# Bf706_DSP.net
KiCad netlist of a schematic drawn in Altium Designer
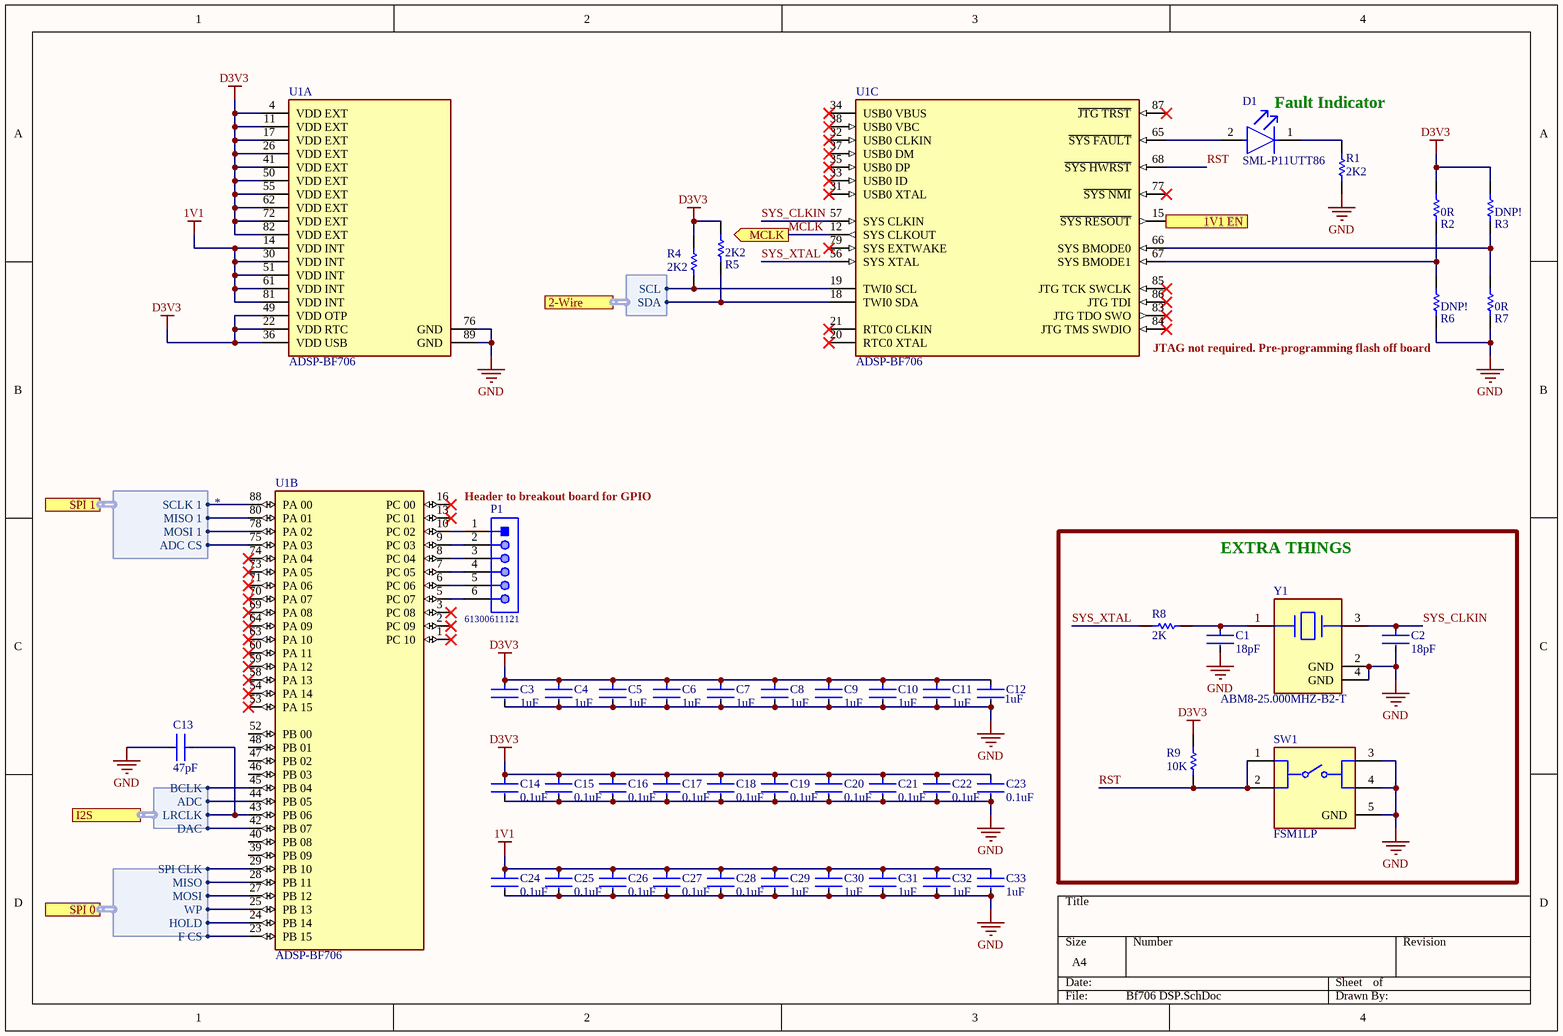
[diagram p0: Bf706 DSP.SchDoc]

(export (version "E")
  (design (tool "Eeschema 10.0.6"))
  (components
    (comp (ref "C1")
      (value "18pF")
      (footprint "FP-GRM15-MFG")
      (description "CAP CER 0.1UF 16V X7R 0402")
      (fields (field (name "MANUFACTURER PART NUMBER") "GRM155R71C104KA88D") (field (name "TOLERANCE") "10%"))
      (libsource (lib "Altium Content Vault") (part "236180d848d6139a670b325ea6854c9"))
    )
    (comp (ref "C2")
      (value "18pF")
      (footprint "FP-GRM15-MFG")
      (description "CAP CER 0.1UF 16V X7R 0402")
      (fields (field (name "MANUFACTURER PART NUMBER") "GRM155R71C104KA88D") (field (name "TOLERANCE") "10%"))
      (libsource (lib "Altium Content Vault") (part "236180d848d6139a670b325ea6854c9"))
    )
    (comp (ref "C3")
      (value "1uF")
      (footprint "FP-GRM15-MFG")
      (description "CAP CER 0.1UF 16V X7R 0402")
      (fields (field (name "MANUFACTURER PART NUMBER") "GRM155R71C104KA88D") (field (name "TOLERANCE") "10%"))
      (libsource (lib "Altium Content Vault") (part "236180d848d6139a670b325ea6854c9"))
    )
    (comp (ref "C4")
      (value "1uF")
      (footprint "FP-GRM15-MFG")
      (description "CAP CER 0.1UF 16V X7R 0402")
      (fields (field (name "MANUFACTURER PART NUMBER") "GRM155R71C104KA88D") (field (name "TOLERANCE") "10%"))
      (libsource (lib "Altium Content Vault") (part "236180d848d6139a670b325ea6854c9"))
    )
    (comp (ref "C5")
      (value "1uF")
      (footprint "FP-GRM15-MFG")
      (description "CAP CER 0.1UF 16V X7R 0402")
      (fields (field (name "MANUFACTURER PART NUMBER") "GRM155R71C104KA88D") (field (name "TOLERANCE") "10%"))
      (libsource (lib "Altium Content Vault") (part "236180d848d6139a670b325ea6854c9"))
    )
    (comp (ref "C6")
      (value "1uF")
      (footprint "FP-GRM15-MFG")
      (description "CAP CER 0.1UF 16V X7R 0402")
      (fields (field (name "MANUFACTURER PART NUMBER") "GRM155R71C104KA88D") (field (name "TOLERANCE") "10%"))
      (libsource (lib "Altium Content Vault") (part "236180d848d6139a670b325ea6854c9"))
    )
    (comp (ref "C7")
      (value "1uF")
      (footprint "FP-GRM15-MFG")
      (description "CAP CER 0.1UF 16V X7R 0402")
      (fields (field (name "MANUFACTURER PART NUMBER") "GRM155R71C104KA88D") (field (name "TOLERANCE") "10%"))
      (libsource (lib "Altium Content Vault") (part "236180d848d6139a670b325ea6854c9"))
    )
    (comp (ref "C8")
      (value "1uF")
      (footprint "FP-GRM15-MFG")
      (description "CAP CER 0.1UF 16V X7R 0402")
      (fields (field (name "MANUFACTURER PART NUMBER") "GRM155R71C104KA88D") (field (name "TOLERANCE") "10%"))
      (libsource (lib "Altium Content Vault") (part "236180d848d6139a670b325ea6854c9"))
    )
    (comp (ref "C9")
      (value "1uF")
      (footprint "FP-GRM15-MFG")
      (description "CAP CER 0.1UF 16V X7R 0402")
      (fields (field (name "MANUFACTURER PART NUMBER") "GRM155R71C104KA88D") (field (name "TOLERANCE") "10%"))
      (libsource (lib "Altium Content Vault") (part "236180d848d6139a670b325ea6854c9"))
    )
    (comp (ref "C10")
      (value "1uF")
      (footprint "FP-GRM15-MFG")
      (description "CAP CER 0.1UF 16V X7R 0402")
      (fields (field (name "MANUFACTURER PART NUMBER") "GRM155R71C104KA88D") (field (name "TOLERANCE") "10%"))
      (libsource (lib "Altium Content Vault") (part "236180d848d6139a670b325ea6854c9"))
    )
    (comp (ref "C11")
      (value "1uF")
      (footprint "FP-GRM15-MFG")
      (description "CAP CER 0.1UF 16V X7R 0402")
      (fields (field (name "MANUFACTURER PART NUMBER") "GRM155R71C104KA88D") (field (name "TOLERANCE") "10%"))
      (libsource (lib "Altium Content Vault") (part "236180d848d6139a670b325ea6854c9"))
    )
    (comp (ref "C12")
      (value "1uF")
      (footprint "FP-GRM15-MFG")
      (description "CAP CER 0.1UF 16V X7R 0402")
      (fields (field (name "MANUFACTURER PART NUMBER") "GRM155R71C104KA88D") (field (name "TOLERANCE") "10%"))
      (libsource (lib "Altium Content Vault") (part "236180d848d6139a670b325ea6854c9"))
    )
    (comp (ref "C13")
      (value "47pF")
      (footprint "FP-GRM15-MFG")
      (description "CAP CER 0.1UF 16V X7R 0402")
      (fields (field (name "MANUFACTURER PART NUMBER") "GRM155R71C104KA88D") (field (name "TOLERANCE") "10%"))
      (libsource (lib "Altium Content Vault") (part "236180d848d6139a670b325ea6854c9"))
    )
    (comp (ref "C14")
      (value "0.1uF")
      (footprint "FP-GRM15-MFG")
      (description "CAP CER 0.1UF 16V X7R 0402")
      (fields (field (name "MANUFACTURER PART NUMBER") "GRM155R71C104KA88D") (field (name "TOLERANCE") "10%"))
      (libsource (lib "Altium Content Vault") (part "236180d848d6139a670b325ea6854c9"))
    )
    (comp (ref "C15")
      (value "0.1uF")
      (footprint "FP-GRM15-MFG")
      (description "CAP CER 0.1UF 16V X7R 0402")
      (fields (field (name "MANUFACTURER PART NUMBER") "GRM155R71C104KA88D") (field (name "TOLERANCE") "10%"))
      (libsource (lib "Altium Content Vault") (part "236180d848d6139a670b325ea6854c9"))
    )
    (comp (ref "C16")
      (value "0.1uF")
      (footprint "FP-GRM15-MFG")
      (description "CAP CER 0.1UF 16V X7R 0402")
      (fields (field (name "MANUFACTURER PART NUMBER") "GRM155R71C104KA88D") (field (name "TOLERANCE") "10%"))
      (libsource (lib "Altium Content Vault") (part "236180d848d6139a670b325ea6854c9"))
    )
    (comp (ref "C17")
      (value "0.1uF")
      (footprint "FP-GRM15-MFG")
      (description "CAP CER 0.1UF 16V X7R 0402")
      (fields (field (name "MANUFACTURER PART NUMBER") "GRM155R71C104KA88D") (field (name "TOLERANCE") "10%"))
      (libsource (lib "Altium Content Vault") (part "236180d848d6139a670b325ea6854c9"))
    )
    (comp (ref "C18")
      (value "0.1uF")
      (footprint "FP-GRM15-MFG")
      (description "CAP CER 0.1UF 16V X7R 0402")
      (fields (field (name "MANUFACTURER PART NUMBER") "GRM155R71C104KA88D") (field (name "TOLERANCE") "10%"))
      (libsource (lib "Altium Content Vault") (part "236180d848d6139a670b325ea6854c9"))
    )
    (comp (ref "C19")
      (value "0.1uF")
      (footprint "FP-GRM15-MFG")
      (description "CAP CER 0.1UF 16V X7R 0402")
      (fields (field (name "MANUFACTURER PART NUMBER") "GRM155R71C104KA88D") (field (name "TOLERANCE") "10%"))
      (libsource (lib "Altium Content Vault") (part "236180d848d6139a670b325ea6854c9"))
    )
    (comp (ref "C20")
      (value "0.1uF")
      (footprint "FP-GRM15-MFG")
      (description "CAP CER 0.1UF 16V X7R 0402")
      (fields (field (name "MANUFACTURER PART NUMBER") "GRM155R71C104KA88D") (field (name "TOLERANCE") "10%"))
      (libsource (lib "Altium Content Vault") (part "236180d848d6139a670b325ea6854c9"))
    )
    (comp (ref "C21")
      (value "0.1uF")
      (footprint "FP-GRM15-MFG")
      (description "CAP CER 0.1UF 16V X7R 0402")
      (fields (field (name "MANUFACTURER PART NUMBER") "GRM155R71C104KA88D") (field (name "TOLERANCE") "10%"))
      (libsource (lib "Altium Content Vault") (part "236180d848d6139a670b325ea6854c9"))
    )
    (comp (ref "C22")
      (value "0.1uF")
      (footprint "FP-GRM15-MFG")
      (description "CAP CER 0.1UF 16V X7R 0402")
      (fields (field (name "MANUFACTURER PART NUMBER") "GRM155R71C104KA88D") (field (name "TOLERANCE") "10%"))
      (libsource (lib "Altium Content Vault") (part "236180d848d6139a670b325ea6854c9"))
    )
    (comp (ref "C23")
      (value "0.1uF")
      (footprint "FP-GRM15-MFG")
      (description "CAP CER 0.1UF 16V X7R 0402")
      (fields (field (name "MANUFACTURER PART NUMBER") "GRM155R71C104KA88D") (field (name "TOLERANCE") "10%"))
      (libsource (lib "Altium Content Vault") (part "236180d848d6139a670b325ea6854c9"))
    )
    (comp (ref "C24")
      (value "0.1uF")
      (footprint "FP-GRM15-MFG")
      (description "CAP CER 0.1UF 16V X7R 0402")
      (fields (field (name "MANUFACTURER PART NUMBER") "GRM155R71C104KA88D") (field (name "TOLERANCE") "10%"))
      (libsource (lib "Altium Content Vault") (part "236180d848d6139a670b325ea6854c9"))
    )
    (comp (ref "C25")
      (value "0.1uF")
      (footprint "FP-GRM15-MFG")
      (description "CAP CER 0.1UF 16V X7R 0402")
      (fields (field (name "MANUFACTURER PART NUMBER") "GRM155R71C104KA88D") (field (name "TOLERANCE") "10%"))
      (libsource (lib "Altium Content Vault") (part "236180d848d6139a670b325ea6854c9"))
    )
    (comp (ref "C26")
      (value "0.1uF")
      (footprint "FP-GRM15-MFG")
      (description "CAP CER 0.1UF 16V X7R 0402")
      (fields (field (name "MANUFACTURER PART NUMBER") "GRM155R71C104KA88D") (field (name "TOLERANCE") "10%"))
      (libsource (lib "Altium Content Vault") (part "236180d848d6139a670b325ea6854c9"))
    )
    (comp (ref "C27")
      (value "0.1uF")
      (footprint "FP-GRM15-MFG")
      (description "CAP CER 0.1UF 16V X7R 0402")
      (fields (field (name "MANUFACTURER PART NUMBER") "GRM155R71C104KA88D") (field (name "TOLERANCE") "10%"))
      (libsource (lib "Altium Content Vault") (part "236180d848d6139a670b325ea6854c9"))
    )
    (comp (ref "C28")
      (value "0.1uF")
      (footprint "FP-GRM15-MFG")
      (description "CAP CER 0.1UF 16V X7R 0402")
      (fields (field (name "MANUFACTURER PART NUMBER") "GRM155R71C104KA88D") (field (name "TOLERANCE") "10%"))
      (libsource (lib "Altium Content Vault") (part "236180d848d6139a670b325ea6854c9"))
    )
    (comp (ref "C29")
      (value "1uF")
      (footprint "FP-GRM15-MFG")
      (description "CAP CER 0.1UF 16V X7R 0402")
      (fields (field (name "MANUFACTURER PART NUMBER") "GRM155R71C104KA88D") (field (name "TOLERANCE") "10%"))
      (libsource (lib "Altium Content Vault") (part "236180d848d6139a670b325ea6854c9"))
    )
    (comp (ref "C30")
      (value "1uF")
      (footprint "FP-GRM15-MFG")
      (description "CAP CER 0.1UF 16V X7R 0402")
      (fields (field (name "MANUFACTURER PART NUMBER") "GRM155R71C104KA88D") (field (name "TOLERANCE") "10%"))
      (libsource (lib "Altium Content Vault") (part "236180d848d6139a670b325ea6854c9"))
    )
    (comp (ref "C31")
      (value "1uF")
      (footprint "FP-GRM15-MFG")
      (description "CAP CER 0.1UF 16V X7R 0402")
      (fields (field (name "MANUFACTURER PART NUMBER") "GRM155R71C104KA88D") (field (name "TOLERANCE") "10%"))
      (libsource (lib "Altium Content Vault") (part "236180d848d6139a670b325ea6854c9"))
    )
    (comp (ref "C32")
      (value "1uF")
      (footprint "FP-GRM15-MFG")
      (description "CAP CER 0.1UF 16V X7R 0402")
      (fields (field (name "MANUFACTURER PART NUMBER") "GRM155R71C104KA88D") (field (name "TOLERANCE") "10%"))
      (libsource (lib "Altium Content Vault") (part "236180d848d6139a670b325ea6854c9"))
    )
    (comp (ref "C33")
      (value "1uF")
      (footprint "FP-GRM15-MFG")
      (description "CAP CER 0.1UF 16V X7R 0402")
      (fields (field (name "MANUFACTURER PART NUMBER") "GRM155R71C104KA88D") (field (name "TOLERANCE") "10%"))
      (libsource (lib "Altium Content Vault") (part "236180d848d6139a670b325ea6854c9"))
    )
    (comp (ref "D1")
      (value "SML-P11UTT86")
      (footprint "FP-SML-P11UTT86-MFG")
      (description "LED RED CLEAR 1006 SMD")
      (libsource (lib "Altium Content Vault") (part "8706943c75ba83719d021d2fdc84c58"))
    )
    (comp (ref "P1")
      (value "61300611121")
      (footprint "61300611121")
      (description "THT Vertical Pin Header WR-PHD, Pitch 2.54 mm, Single Row, 6 pins")
      (fields (field (name "MANUFACTURER") "Wurth Elektronik") (field (name "PUBLISHER") "WurthElektronik"))
      (libsource (lib "Altium Content Vault") (part "WE-CN-1P-M-R6"))
    )
    (comp (ref "R1")
      (value "2K2")
      (footprint "RESC1005X40X25LL05T05")
      (description "Chip Resistor, 0 Ohm, 0.1 W, -55 to 155 degC, 0402 (1005 Metric), RoHS, Tape and Reel")
      (fields (field (name "MANUFACTURER") "Panasonic") (field (name "TOLERANCE") "5%"))
      (libsource (lib "Altium Content Vault") (part "RES-2"))
    )
    (comp (ref "R2")
      (value "0R")
      (footprint "RESC1005X40X25LL05T05")
      (description "Chip Resistor, 0 Ohm, 0.1 W, -55 to 155 degC, 0402 (1005 Metric), RoHS, Tape and Reel")
      (fields (field (name "MANUFACTURER") "Panasonic") (field (name "TOLERANCE") "5%"))
      (libsource (lib "Altium Content Vault") (part "RES-2"))
    )
    (comp (ref "R3")
      (value "DNP!")
      (footprint "RESC1005X40X25LL05T05")
      (description "Chip Resistor, 0 Ohm, 0.1 W, -55 to 155 degC, 0402 (1005 Metric), RoHS, Tape and Reel")
      (fields (field (name "MANUFACTURER") "Panasonic") (field (name "TOLERANCE") "5%"))
      (libsource (lib "Altium Content Vault") (part "RES-2"))
    )
    (comp (ref "R4")
      (value "2K2")
      (footprint "RESC1005X40X25LL05T05")
      (description "Chip Resistor, 0 Ohm, 0.1 W, -55 to 155 degC, 0402 (1005 Metric), RoHS, Tape and Reel")
      (fields (field (name "MANUFACTURER") "Panasonic") (field (name "TOLERANCE") "5%"))
      (libsource (lib "Altium Content Vault") (part "RES-2"))
    )
    (comp (ref "R5")
      (value "2K2")
      (footprint "RESC1005X40X25LL05T05")
      (description "Chip Resistor, 0 Ohm, 0.1 W, -55 to 155 degC, 0402 (1005 Metric), RoHS, Tape and Reel")
      (fields (field (name "MANUFACTURER") "Panasonic") (field (name "TOLERANCE") "5%"))
      (libsource (lib "Altium Content Vault") (part "RES-2"))
    )
    (comp (ref "R6")
      (value "DNP!")
      (footprint "RESC1005X40X25LL05T05")
      (description "Chip Resistor, 0 Ohm, 0.1 W, -55 to 155 degC, 0402 (1005 Metric), RoHS, Tape and Reel")
      (fields (field (name "MANUFACTURER") "Panasonic") (field (name "TOLERANCE") "5%"))
      (libsource (lib "Altium Content Vault") (part "RES-2"))
    )
    (comp (ref "R7")
      (value "0R")
      (footprint "RESC1005X40X25LL05T05")
      (description "Chip Resistor, 0 Ohm, 0.1 W, -55 to 155 degC, 0402 (1005 Metric), RoHS, Tape and Reel")
      (fields (field (name "MANUFACTURER") "Panasonic") (field (name "TOLERANCE") "5%"))
      (libsource (lib "Altium Content Vault") (part "RES-2"))
    )
    (comp (ref "R8")
      (value "2K")
      (footprint "RESC1005X40X25LL05T05")
      (description "Chip Resistor, 0 Ohm, 0.1 W, -55 to 155 degC, 0402 (1005 Metric), RoHS, Tape and Reel")
      (fields (field (name "MANUFACTURER") "Panasonic") (field (name "TOLERANCE") "5%"))
      (libsource (lib "Altium Content Vault") (part "RES-2"))
    )
    (comp (ref "R9")
      (value "10K")
      (footprint "RESC1005X40X25LL05T05")
      (description "Chip Resistor, 0 Ohm, 0.1 W, -55 to 155 degC, 0402 (1005 Metric), RoHS, Tape and Reel")
      (fields (field (name "MANUFACTURER") "Panasonic") (field (name "TOLERANCE") "5%"))
      (libsource (lib "Altium Content Vault") (part "RES-2"))
    )
    (comp (ref "SW1")
      (value "FSM1LP")
      (footprint "FP-FSM1LP-MFG")
      (description "SWITCH TACTILE SPST-NO 0.05A 24V")
      (libsource (lib "Altium Content Vault") (part "3a9e64be5c1b186b34f28721102267a"))
    )
    (comp (ref "U1")
      (value "ADSP-BF706")
      (footprint "FP-CP-88-8-IPC_C")
      (description "IC DSP LP 128KB L2SR 88LFCSP")
      (libsource (lib "Altium Content Vault") (part "f148b48c6e4e4aed1bc29808ef88166"))
    )
    (comp (ref "Y1")
      (value "ABM8-25.000MHZ-B2-T")
      (footprint "FP-ABM8-MFG")
      (description "Crystal 25MHz ±20ppm 18pF SMD-4 3.2mm x 2.5mm")
      (fields (field (name "TOLERANCE") "20ppm"))
      (libsource (lib "Altium Content Vault") (part "dfdb7f9a12507849fb681da9a70121c"))
    )
  )
  (nets
    (net (code "6") (name "/1V1 EN") (class "Default")
      (node (ref "U1") (pin "15") (pinfunction "~{SYS_RESOUT}_15") (pintype "output"))
    )
    (net (code "7") (name "/ADC") (class "Default")
      (node (ref "U1") (pin "44") (pinfunction "PB_05_44") (pintype "bidirectional"))
    )
    (net (code "8") (name "/ADC CS") (class "Default")
      (node (ref "U1") (pin "75") (pinfunction "PA_03_75") (pintype "bidirectional"))
    )
    (net (code "9") (name "/BCLK") (class "Default")
      (node (ref "U1") (pin "45") (pinfunction "PB_04_45") (pintype "bidirectional"))
    )
    (net (code "10") (name "/DAC") (class "Default")
      (node (ref "U1") (pin "42") (pinfunction "PB_07_42") (pintype "bidirectional"))
    )
    (net (code "11") (name "/F CS") (class "Default")
      (node (ref "U1") (pin "23") (pinfunction "PB_15_23") (pintype "bidirectional"))
    )
    (net (code "12") (name "/HOLD") (class "Default")
      (node (ref "U1") (pin "24") (pinfunction "PB_14_24") (pintype "bidirectional"))
    )
    (net (code "13") (name "/LRCLK") (class "Default")
      (node (ref "C13") (pin "2") (pinfunction "2_2") (pintype "passive"))
      (node (ref "U1") (pin "43") (pinfunction "PB_06_43") (pintype "bidirectional"))
    )
    (net (code "14") (name "/MCLK") (class "Default")
      (node (ref "U1") (pin "12") (pinfunction "SYS_CLKOUT_12") (pintype "output"))
    )
    (net (code "15") (name "/MISO") (class "Default")
      (node (ref "U1") (pin "28") (pinfunction "PB_11_28") (pintype "bidirectional"))
    )
    (net (code "16") (name "/MISO 1") (class "Default")
      (node (ref "U1") (pin "80") (pinfunction "PA_01_80") (pintype "bidirectional"))
    )
    (net (code "17") (name "/MOSI") (class "Default")
      (node (ref "U1") (pin "27") (pinfunction "PB_12_27") (pintype "bidirectional"))
    )
    (net (code "18") (name "/MOSI 1") (class "Default")
      (node (ref "U1") (pin "78") (pinfunction "PA_02_78") (pintype "bidirectional"))
    )
    (net (code "19") (name "/RST") (class "Default")
      (node (ref "R9") (pin "1") (pinfunction "1_1") (pintype "passive"))
      (node (ref "SW1") (pin "1") (pinfunction "1_1") (pintype "passive"))
      (node (ref "SW1") (pin "2") (pinfunction "2_2") (pintype "passive"))
      (node (ref "U1") (pin "68") (pinfunction "~{SYS_HWRST}_68") (pintype "input"))
    )
    (net (code "20") (name "/SCL") (class "Default")
      (node (ref "R4") (pin "1") (pinfunction "1_1") (pintype "passive"))
      (node (ref "U1") (pin "19") (pinfunction "TWI0_SCL_19") (pintype "passive"))
    )
    (net (code "21") (name "/SCLK 1") (class "Default")
      (node (ref "U1") (pin "88") (pinfunction "PA_00_88") (pintype "bidirectional"))
    )
    (net (code "22") (name "/SDA") (class "Default")
      (node (ref "R5") (pin "1") (pinfunction "1_1") (pintype "passive"))
      (node (ref "U1") (pin "18") (pinfunction "TWI0_SDA_18") (pintype "passive"))
    )
    (net (code "23") (name "/SPI CLK") (class "Default")
      (node (ref "U1") (pin "29") (pinfunction "PB_10_29") (pintype "bidirectional"))
    )
    (net (code "24") (name "/SYS_CLKIN") (class "Default")
      (node (ref "C2") (pin "2") (pinfunction "2_2") (pintype "passive"))
      (node (ref "U1") (pin "57") (pinfunction "SYS_CLKIN_57") (pintype "input"))
      (node (ref "Y1") (pin "3") (pinfunction "3_3") (pintype "passive"))
    )
    (net (code "25") (name "/SYS_XTAL") (class "Default")
      (node (ref "R8") (pin "2") (pinfunction "2_2") (pintype "passive"))
      (node (ref "U1") (pin "56") (pinfunction "SYS_XTAL_56") (pintype "input"))
    )
    (net (code "26") (name "/WP") (class "Default")
      (node (ref "U1") (pin "25") (pinfunction "PB_13_25") (pintype "bidirectional"))
    )
    (net (code "31") (name "1V1") (class "Default")
      (node (ref "C24") (pin "2") (pinfunction "2_2") (pintype "passive"))
      (node (ref "C25") (pin "2") (pinfunction "2_2") (pintype "passive"))
      (node (ref "C26") (pin "2") (pinfunction "2_2") (pintype "passive"))
      (node (ref "C27") (pin "2") (pinfunction "2_2") (pintype "passive"))
      (node (ref "C28") (pin "2") (pinfunction "2_2") (pintype "passive"))
      (node (ref "C29") (pin "2") (pinfunction "2_2") (pintype "passive"))
      (node (ref "C30") (pin "2") (pinfunction "2_2") (pintype "passive"))
      (node (ref "C31") (pin "2") (pinfunction "2_2") (pintype "passive"))
      (node (ref "C32") (pin "2") (pinfunction "2_2") (pintype "passive"))
      (node (ref "C33") (pin "2") (pinfunction "2_2") (pintype "passive"))
      (node (ref "U1") (pin "14") (pinfunction "VDD_INT_14") (pintype "power_in"))
      (node (ref "U1") (pin "30") (pinfunction "VDD_INT_30") (pintype "power_in"))
      (node (ref "U1") (pin "51") (pinfunction "VDD_INT_51") (pintype "power_in"))
      (node (ref "U1") (pin "61") (pinfunction "VDD_INT_61") (pintype "power_in"))
      (node (ref "U1") (pin "81") (pinfunction "VDD_INT_81") (pintype "power_in"))
    )
    (net (code "32") (name "D3V3") (class "Default")
      (node (ref "C10") (pin "2") (pinfunction "2_2") (pintype "passive"))
      (node (ref "C11") (pin "2") (pinfunction "2_2") (pintype "passive"))
      (node (ref "C12") (pin "2") (pinfunction "2_2") (pintype "passive"))
      (node (ref "C14") (pin "2") (pinfunction "2_2") (pintype "passive"))
      (node (ref "C15") (pin "2") (pinfunction "2_2") (pintype "passive"))
      (node (ref "C16") (pin "2") (pinfunction "2_2") (pintype "passive"))
      (node (ref "C17") (pin "2") (pinfunction "2_2") (pintype "passive"))
      (node (ref "C18") (pin "2") (pinfunction "2_2") (pintype "passive"))
      (node (ref "C19") (pin "2") (pinfunction "2_2") (pintype "passive"))
      (node (ref "C20") (pin "2") (pinfunction "2_2") (pintype "passive"))
      (node (ref "C21") (pin "2") (pinfunction "2_2") (pintype "passive"))
      (node (ref "C22") (pin "2") (pinfunction "2_2") (pintype "passive"))
      (node (ref "C23") (pin "2") (pinfunction "2_2") (pintype "passive"))
      (node (ref "C3") (pin "2") (pinfunction "2_2") (pintype "passive"))
      (node (ref "C4") (pin "2") (pinfunction "2_2") (pintype "passive"))
      (node (ref "C5") (pin "2") (pinfunction "2_2") (pintype "passive"))
      (node (ref "C6") (pin "2") (pinfunction "2_2") (pintype "passive"))
      (node (ref "C7") (pin "2") (pinfunction "2_2") (pintype "passive"))
      (node (ref "C8") (pin "2") (pinfunction "2_2") (pintype "passive"))
      (node (ref "C9") (pin "2") (pinfunction "2_2") (pintype "passive"))
      (node (ref "R2") (pin "2") (pinfunction "2_2") (pintype "passive"))
      (node (ref "R3") (pin "2") (pinfunction "2_2") (pintype "passive"))
      (node (ref "R4") (pin "2") (pinfunction "2_2") (pintype "passive"))
      (node (ref "R5") (pin "2") (pinfunction "2_2") (pintype "passive"))
      (node (ref "R9") (pin "2") (pinfunction "2_2") (pintype "passive"))
      (node (ref "U1") (pin "11") (pinfunction "VDD_EXT_11") (pintype "power_in"))
      (node (ref "U1") (pin "17") (pinfunction "VDD_EXT_17") (pintype "power_in"))
      (node (ref "U1") (pin "22") (pinfunction "VDD_RTC_22") (pintype "power_in"))
      (node (ref "U1") (pin "26") (pinfunction "VDD_EXT_26") (pintype "power_in"))
      (node (ref "U1") (pin "36") (pinfunction "VDD_USB_36") (pintype "power_in"))
      (node (ref "U1") (pin "4") (pinfunction "VDD_EXT_4") (pintype "power_in"))
      (node (ref "U1") (pin "41") (pinfunction "VDD_EXT_41") (pintype "power_in"))
      (node (ref "U1") (pin "49") (pinfunction "VDD_OTP_49") (pintype "power_in"))
      (node (ref "U1") (pin "50") (pinfunction "VDD_EXT_50") (pintype "power_in"))
      (node (ref "U1") (pin "55") (pinfunction "VDD_EXT_55") (pintype "power_in"))
      (node (ref "U1") (pin "62") (pinfunction "VDD_EXT_62") (pintype "power_in"))
      (node (ref "U1") (pin "72") (pinfunction "VDD_EXT_72") (pintype "power_in"))
      (node (ref "U1") (pin "82") (pinfunction "VDD_EXT_82") (pintype "power_in"))
    )
    (net (code "33") (name "GND") (class "Default")
      (node (ref "C1") (pin "1") (pinfunction "1_1") (pintype "passive"))
      (node (ref "C10") (pin "1") (pinfunction "1_1") (pintype "passive"))
      (node (ref "C11") (pin "1") (pinfunction "1_1") (pintype "passive"))
      (node (ref "C12") (pin "1") (pinfunction "1_1") (pintype "passive"))
      (node (ref "C13") (pin "1") (pinfunction "1_1") (pintype "passive"))
      (node (ref "C14") (pin "1") (pinfunction "1_1") (pintype "passive"))
      (node (ref "C15") (pin "1") (pinfunction "1_1") (pintype "passive"))
      (node (ref "C16") (pin "1") (pinfunction "1_1") (pintype "passive"))
      (node (ref "C17") (pin "1") (pinfunction "1_1") (pintype "passive"))
      (node (ref "C18") (pin "1") (pinfunction "1_1") (pintype "passive"))
      (node (ref "C19") (pin "1") (pinfunction "1_1") (pintype "passive"))
      (node (ref "C2") (pin "1") (pinfunction "1_1") (pintype "passive"))
      (node (ref "C20") (pin "1") (pinfunction "1_1") (pintype "passive"))
      (node (ref "C21") (pin "1") (pinfunction "1_1") (pintype "passive"))
      (node (ref "C22") (pin "1") (pinfunction "1_1") (pintype "passive"))
      (node (ref "C23") (pin "1") (pinfunction "1_1") (pintype "passive"))
      (node (ref "C24") (pin "1") (pinfunction "1_1") (pintype "passive"))
      (node (ref "C25") (pin "1") (pinfunction "1_1") (pintype "passive"))
      (node (ref "C26") (pin "1") (pinfunction "1_1") (pintype "passive"))
      (node (ref "C27") (pin "1") (pinfunction "1_1") (pintype "passive"))
      (node (ref "C28") (pin "1") (pinfunction "1_1") (pintype "passive"))
      (node (ref "C29") (pin "1") (pinfunction "1_1") (pintype "passive"))
      (node (ref "C3") (pin "1") (pinfunction "1_1") (pintype "passive"))
      (node (ref "C30") (pin "1") (pinfunction "1_1") (pintype "passive"))
      (node (ref "C31") (pin "1") (pinfunction "1_1") (pintype "passive"))
      (node (ref "C32") (pin "1") (pinfunction "1_1") (pintype "passive"))
      (node (ref "C33") (pin "1") (pinfunction "1_1") (pintype "passive"))
      (node (ref "C4") (pin "1") (pinfunction "1_1") (pintype "passive"))
      (node (ref "C5") (pin "1") (pinfunction "1_1") (pintype "passive"))
      (node (ref "C6") (pin "1") (pinfunction "1_1") (pintype "passive"))
      (node (ref "C7") (pin "1") (pinfunction "1_1") (pintype "passive"))
      (node (ref "C8") (pin "1") (pinfunction "1_1") (pintype "passive"))
      (node (ref "C9") (pin "1") (pinfunction "1_1") (pintype "passive"))
      (node (ref "R1") (pin "1") (pinfunction "1_1") (pintype "passive"))
      (node (ref "R6") (pin "1") (pinfunction "1_1") (pintype "passive"))
      (node (ref "R7") (pin "1") (pinfunction "1_1") (pintype "passive"))
      (node (ref "SW1") (pin "3") (pinfunction "3_3") (pintype "passive"))
      (node (ref "SW1") (pin "4") (pinfunction "4_4") (pintype "passive"))
      (node (ref "SW1") (pin "5") (pinfunction "GND_5") (pintype "power_in"))
      (node (ref "U1") (pin "76") (pinfunction "GND_76") (pintype "power_in"))
      (node (ref "U1") (pin "89") (pinfunction "GND_89") (pintype "power_in"))
      (node (ref "Y1") (pin "2") (pinfunction "GND_2") (pintype "power_in"))
      (node (ref "Y1") (pin "4") (pinfunction "GND_4") (pintype "power_in"))
    )
    (net (code "34") (name "Net-(C1-Pad2)") (class "Default")
      (node (ref "C1") (pin "2") (pinfunction "2_2") (pintype "passive"))
      (node (ref "R8") (pin "1") (pinfunction "1_1") (pintype "passive"))
      (node (ref "Y1") (pin "1") (pinfunction "1_1") (pintype "passive"))
    )
    (net (code "35") (name "Net-(D1-A)") (class "Default")
      (node (ref "D1") (pin "2") (pinfunction "A_2") (pintype "passive"))
      (node (ref "U1") (pin "65") (pinfunction "~{SYS_FAULT}_65") (pintype "input"))
    )
    (net (code "36") (name "Net-(D1-C)") (class "Default")
      (node (ref "D1") (pin "1") (pinfunction "C_1") (pintype "passive"))
      (node (ref "R1") (pin "2") (pinfunction "2_2") (pintype "passive"))
    )
    (net (code "37") (name "Net-(U1B-PC_02)") (class "Default")
      (node (ref "P1") (pin "1") (pinfunction "1_1") (pintype "passive"))
      (node (ref "U1") (pin "10") (pinfunction "PC_02_10") (pintype "bidirectional"))
    )
    (net (code "38") (name "Net-(U1B-PC_03)") (class "Default")
      (node (ref "P1") (pin "2") (pinfunction "2_2") (pintype "passive"))
      (node (ref "U1") (pin "9") (pinfunction "PC_03_9") (pintype "bidirectional"))
    )
    (net (code "39") (name "Net-(U1B-PC_04)") (class "Default")
      (node (ref "P1") (pin "3") (pinfunction "3_3") (pintype "passive"))
      (node (ref "U1") (pin "8") (pinfunction "PC_04_8") (pintype "bidirectional"))
    )
    (net (code "40") (name "Net-(U1B-PC_05)") (class "Default")
      (node (ref "P1") (pin "4") (pinfunction "4_4") (pintype "passive"))
      (node (ref "U1") (pin "7") (pinfunction "PC_05_7") (pintype "bidirectional"))
    )
    (net (code "41") (name "Net-(U1B-PC_06)") (class "Default")
      (node (ref "P1") (pin "5") (pinfunction "5_5") (pintype "passive"))
      (node (ref "U1") (pin "6") (pinfunction "PC_06_6") (pintype "bidirectional"))
    )
    (net (code "42") (name "Net-(U1B-PC_07)") (class "Default")
      (node (ref "P1") (pin "6") (pinfunction "6_6") (pintype "passive"))
      (node (ref "U1") (pin "5") (pinfunction "PC_07_5") (pintype "bidirectional"))
    )
    (net (code "43") (name "Net-(U1C-SYS_BMODE0)") (class "Default")
      (node (ref "R3") (pin "1") (pinfunction "1_1") (pintype "passive"))
      (node (ref "R7") (pin "2") (pinfunction "2_2") (pintype "passive"))
      (node (ref "U1") (pin "66") (pinfunction "SYS_BMODE0_66") (pintype "input"))
    )
    (net (code "44") (name "Net-(U1C-SYS_BMODE1)") (class "Default")
      (node (ref "R2") (pin "1") (pinfunction "1_1") (pintype "passive"))
      (node (ref "R6") (pin "2") (pinfunction "2_2") (pintype "passive"))
      (node (ref "U1") (pin "67") (pinfunction "SYS_BMODE1_67") (pintype "input"))
    )
    (net (code "45") (name "unconnected-(U1B-PA_04-Pad74)") (class "Default")
      (node (ref "U1") (pin "74") (pinfunction "PA_04_74") (pintype "bidirectional+no_connect"))
    )
    (net (code "46") (name "unconnected-(U1B-PA_05-Pad73)") (class "Default")
      (node (ref "U1") (pin "73") (pinfunction "PA_05_73") (pintype "bidirectional+no_connect"))
    )
    (net (code "47") (name "unconnected-(U1B-PA_06-Pad71)") (class "Default")
      (node (ref "U1") (pin "71") (pinfunction "PA_06_71") (pintype "bidirectional+no_connect"))
    )
    (net (code "48") (name "unconnected-(U1B-PA_07-Pad70)") (class "Default")
      (node (ref "U1") (pin "70") (pinfunction "PA_07_70") (pintype "bidirectional+no_connect"))
    )
    (net (code "49") (name "unconnected-(U1B-PA_08-Pad69)") (class "Default")
      (node (ref "U1") (pin "69") (pinfunction "PA_08_69") (pintype "bidirectional+no_connect"))
    )
    (net (code "50") (name "unconnected-(U1B-PA_09-Pad64)") (class "Default")
      (node (ref "U1") (pin "64") (pinfunction "PA_09_64") (pintype "bidirectional+no_connect"))
    )
    (net (code "51") (name "unconnected-(U1B-PA_10-Pad63)") (class "Default")
      (node (ref "U1") (pin "63") (pinfunction "PA_10_63") (pintype "bidirectional+no_connect"))
    )
    (net (code "52") (name "unconnected-(U1B-PA_11-Pad60)") (class "Default")
      (node (ref "U1") (pin "60") (pinfunction "PA_11_60") (pintype "bidirectional+no_connect"))
    )
    (net (code "53") (name "unconnected-(U1B-PA_12-Pad59)") (class "Default")
      (node (ref "U1") (pin "59") (pinfunction "PA_12_59") (pintype "bidirectional+no_connect"))
    )
    (net (code "54") (name "unconnected-(U1B-PA_13-Pad58)") (class "Default")
      (node (ref "U1") (pin "58") (pinfunction "PA_13_58") (pintype "bidirectional+no_connect"))
    )
    (net (code "55") (name "unconnected-(U1B-PA_14-Pad54)") (class "Default")
      (node (ref "U1") (pin "54") (pinfunction "PA_14_54") (pintype "bidirectional+no_connect"))
    )
    (net (code "56") (name "unconnected-(U1B-PA_15-Pad53)") (class "Default")
      (node (ref "U1") (pin "53") (pinfunction "PA_15_53") (pintype "bidirectional+no_connect"))
    )
    (net (code "57") (name "unconnected-(U1B-PB_00-Pad52)") (class "Default")
      (node (ref "U1") (pin "52") (pinfunction "PB_00_52") (pintype "bidirectional"))
    )
    (net (code "58") (name "unconnected-(U1B-PB_01-Pad48)") (class "Default")
      (node (ref "U1") (pin "48") (pinfunction "PB_01_48") (pintype "bidirectional"))
    )
    (net (code "59") (name "unconnected-(U1B-PB_02-Pad47)") (class "Default")
      (node (ref "U1") (pin "47") (pinfunction "PB_02_47") (pintype "bidirectional"))
    )
    (net (code "60") (name "unconnected-(U1B-PB_03-Pad46)") (class "Default")
      (node (ref "U1") (pin "46") (pinfunction "PB_03_46") (pintype "bidirectional"))
    )
    (net (code "61") (name "unconnected-(U1B-PB_08-Pad40)") (class "Default")
      (node (ref "U1") (pin "40") (pinfunction "PB_08_40") (pintype "bidirectional"))
    )
    (net (code "62") (name "unconnected-(U1B-PB_09-Pad39)") (class "Default")
      (node (ref "U1") (pin "39") (pinfunction "PB_09_39") (pintype "bidirectional"))
    )
    (net (code "63") (name "unconnected-(U1B-PC_00-Pad16)") (class "Default")
      (node (ref "U1") (pin "16") (pinfunction "PC_00_16") (pintype "bidirectional+no_connect"))
    )
    (net (code "64") (name "unconnected-(U1B-PC_01-Pad13)") (class "Default")
      (node (ref "U1") (pin "13") (pinfunction "PC_01_13") (pintype "bidirectional+no_connect"))
    )
    (net (code "65") (name "unconnected-(U1B-PC_08-Pad3)") (class "Default")
      (node (ref "U1") (pin "3") (pinfunction "PC_08_3") (pintype "bidirectional+no_connect"))
    )
    (net (code "66") (name "unconnected-(U1B-PC_09-Pad2)") (class "Default")
      (node (ref "U1") (pin "2") (pinfunction "PC_09_2") (pintype "bidirectional+no_connect"))
    )
    (net (code "67") (name "unconnected-(U1B-PC_10-Pad1)") (class "Default")
      (node (ref "U1") (pin "1") (pinfunction "PC_10_1") (pintype "bidirectional+no_connect"))
    )
    (net (code "68") (name "unconnected-(U1C-JTG_TCK_SWCLK-Pad85)") (class "Default")
      (node (ref "U1") (pin "85") (pinfunction "JTG_TCK_SWCLK_85") (pintype "input+no_connect"))
    )
    (net (code "69") (name "unconnected-(U1C-JTG_TDI-Pad86)") (class "Default")
      (node (ref "U1") (pin "86") (pinfunction "JTG_TDI_86") (pintype "input+no_connect"))
    )
    (net (code "70") (name "unconnected-(U1C-JTG_TDO_SWO-Pad83)") (class "Default")
      (node (ref "U1") (pin "83") (pinfunction "JTG_TDO_SWO_83") (pintype "output+no_connect"))
    )
    (net (code "71") (name "unconnected-(U1C-JTG_TMS_SWDIO-Pad84)") (class "Default")
      (node (ref "U1") (pin "84") (pinfunction "JTG_TMS_SWDIO_84") (pintype "input+no_connect"))
    )
    (net (code "72") (name "unconnected-(U1C-RTC0_CLKIN-Pad21)") (class "Default")
      (node (ref "U1") (pin "21") (pinfunction "RTC0_CLKIN_21") (pintype "passive+no_connect"))
    )
    (net (code "73") (name "unconnected-(U1C-RTC0_XTAL-Pad20)") (class "Default")
      (node (ref "U1") (pin "20") (pinfunction "RTC0_XTAL_20") (pintype "passive+no_connect"))
    )
    (net (code "74") (name "unconnected-(U1C-SYS_EXTWAKE-Pad79)") (class "Default")
      (node (ref "U1") (pin "79") (pinfunction "SYS_EXTWAKE_79") (pintype "input+no_connect"))
    )
    (net (code "75") (name "unconnected-(U1C-USB0_CLKIN-Pad32)") (class "Default")
      (node (ref "U1") (pin "32") (pinfunction "USB0_CLKIN_32") (pintype "input+no_connect"))
    )
    (net (code "76") (name "unconnected-(U1C-USB0_DM-Pad37)") (class "Default")
      (node (ref "U1") (pin "37") (pinfunction "USB0_DM_37") (pintype "input+no_connect"))
    )
    (net (code "77") (name "unconnected-(U1C-USB0_DP-Pad35)") (class "Default")
      (node (ref "U1") (pin "35") (pinfunction "USB0_DP_35") (pintype "input+no_connect"))
    )
    (net (code "78") (name "unconnected-(U1C-USB0_ID-Pad33)") (class "Default")
      (node (ref "U1") (pin "33") (pinfunction "USB0_ID_33") (pintype "input+no_connect"))
    )
    (net (code "79") (name "unconnected-(U1C-USB0_VBC-Pad38)") (class "Default")
      (node (ref "U1") (pin "38") (pinfunction "USB0_VBC_38") (pintype "input+no_connect"))
    )
    (net (code "80") (name "unconnected-(U1C-USB0_VBUS-Pad34)") (class "Default")
      (node (ref "U1") (pin "34") (pinfunction "USB0_VBUS_34") (pintype "power_in+no_connect"))
    )
    (net (code "81") (name "unconnected-(U1C-USB0_XTAL-Pad31)") (class "Default")
      (node (ref "U1") (pin "31") (pinfunction "USB0_XTAL_31") (pintype "input+no_connect"))
    )
    (net (code "82") (name "unconnected-(U1C-~{JTG_TRST}-Pad87)") (class "Default")
      (node (ref "U1") (pin "87") (pinfunction "~{JTG_TRST}_87") (pintype "input+no_connect"))
    )
    (net (code "83") (name "unconnected-(U1C-~{SYS_NMI}-Pad77)") (class "Default")
      (node (ref "U1") (pin "77") (pinfunction "~{SYS_NMI}_77") (pintype "input+no_connect"))
    )
  )
)
